# Ethernet.net
KiCad netlist of a schematic drawn in Altium Designer
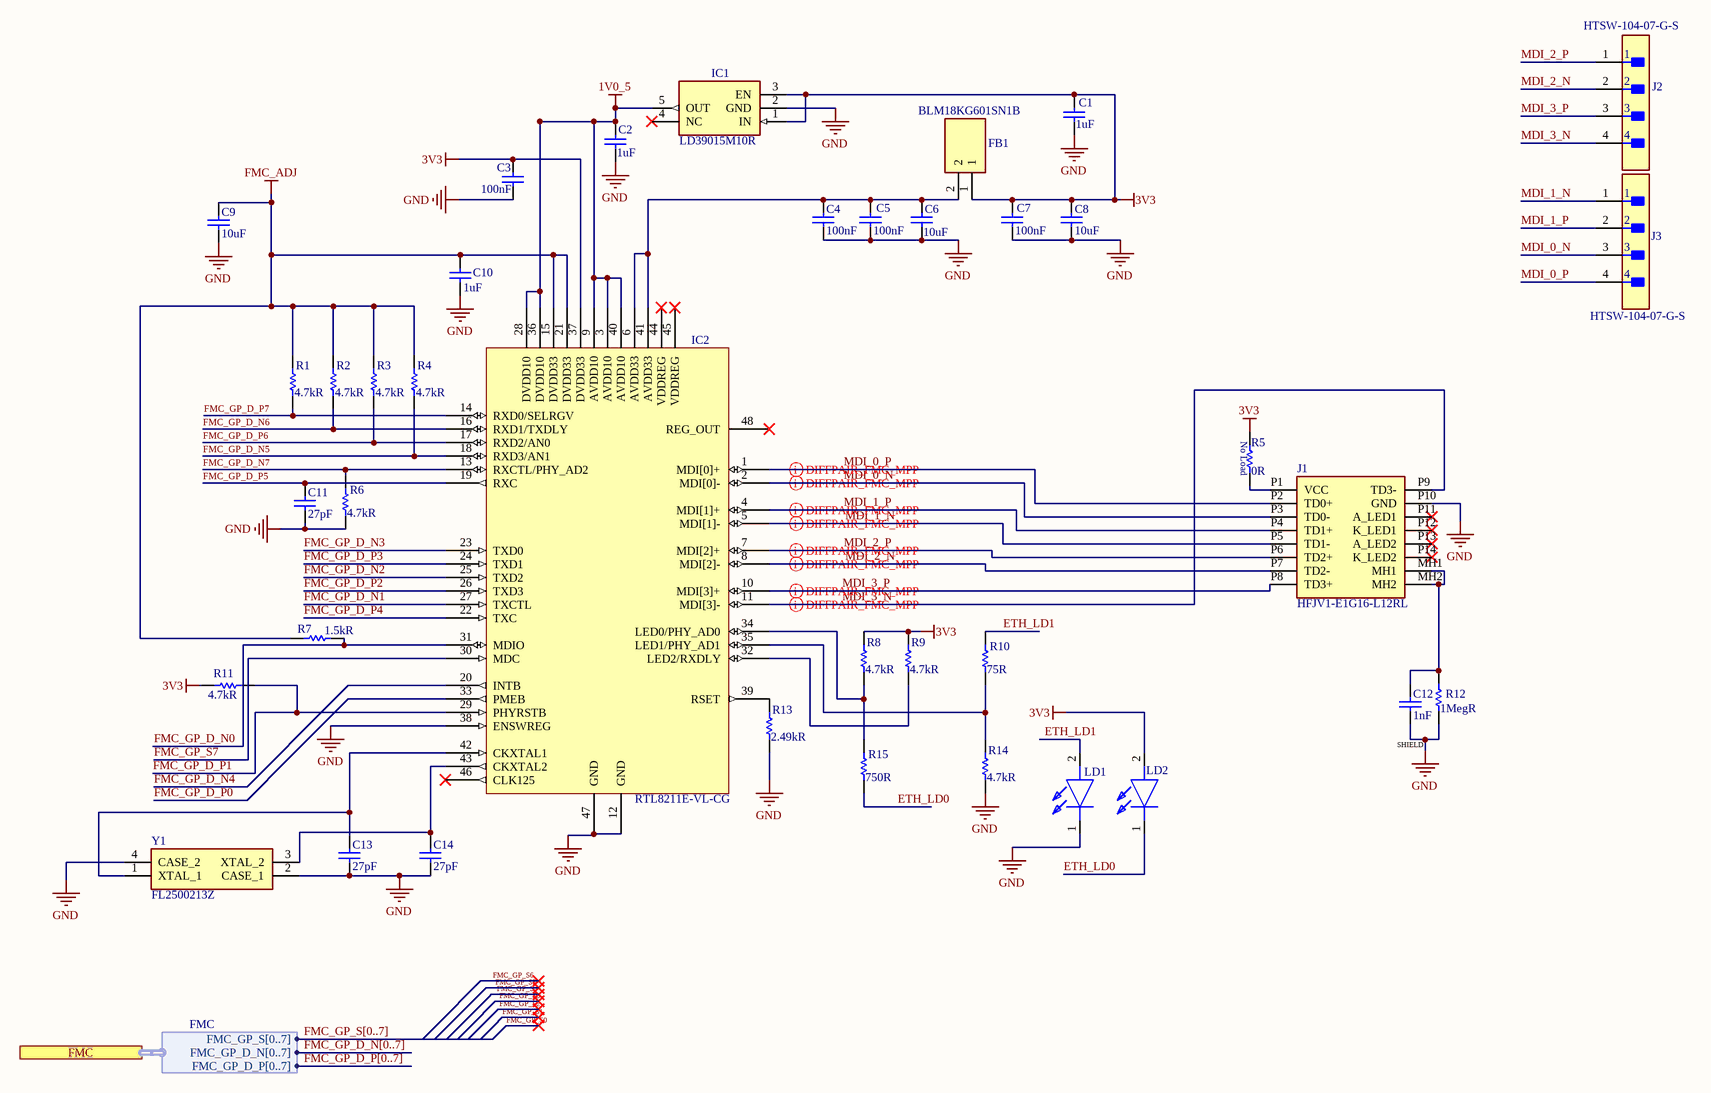
[diagram p0: Ethernet.SchDoc]

(export (version "E")
  (design (tool "Eeschema 10.0.6"))
  (components
    (comp (ref "C1")
      (value "1uF")
      (footprint "CAPC1005X60X30LL05T10")
      (fields
        (field (name "PART NUMBER") "C0402C105K9PACTU")
        (field (name "MANUFACTURER") "Kemet")
        (field (name "TOLERANCE") "10%")
      )
      (libsource (lib "Altium Content Vault") (part "CAP"))
    )
    (comp (ref "C2")
      (value "1uF")
      (footprint "CAPC1005X60X30LL05T10")
      (fields
        (field (name "PART NUMBER") "C0402C105K9PACTU")
        (field (name "MANUFACTURER") "Kemet")
        (field (name "TOLERANCE") "10%")
      )
      (libsource (lib "Altium Content Vault") (part "CAP"))
    )
    (comp (ref "C3")
      (value "100nF")
      (footprint "CAPC1050X55X23LL05T13")
      (description "Chip Capacitor, 100 nF, +/- 10%, 16 V, -55 to 125 degC, 0402 (1005 Metric), RoHS, Tape and Reel")
      (fields
        (field (name "MANUFACTURER") "Samsung Electro-Mechanics")
        (field (name "MANUFACTURER PART NUMBER") "CL05B104KO5NNNC")
      )
      (libsource (lib "Altium Content Vault") (part "CAP-NP-2"))
    )
    (comp (ref "C4")
      (value "100nF")
      (footprint "CAPC1050X55X23LL05T13")
      (description "Chip Capacitor, 100 nF, +/- 10%, 16 V, -55 to 125 degC, 0402 (1005 Metric), RoHS, Tape and Reel")
      (fields
        (field (name "MANUFACTURER") "Samsung Electro-Mechanics")
        (field (name "MANUFACTURER PART NUMBER") "CL05B104KO5NNNC")
      )
      (libsource (lib "Altium Content Vault") (part "CAP-NP-2"))
    )
    (comp (ref "C5")
      (value "100nF")
      (footprint "CAPC1050X55X23LL05T13")
      (description "Chip Capacitor, 100 nF, +/- 10%, 16 V, -55 to 125 degC, 0402 (1005 Metric), RoHS, Tape and Reel")
      (fields
        (field (name "MANUFACTURER") "Samsung Electro-Mechanics")
        (field (name "MANUFACTURER PART NUMBER") "CL05B104KO5NNNC")
      )
      (libsource (lib "Altium Content Vault") (part "CAP-NP-2"))
    )
    (comp (ref "C6")
      (value "10uF")
      (footprint "CAPC1608X90X35LL15T15")
      (fields
        (field (name "MANUFACTURER") "AVX Interconnect / Elco")
        (field (name "PART NUMBER") "06036D106MAT2A")
        (field (name "TOLERANCE") "20%")
      )
      (libsource (lib "Altium Content Vault") (part "CAP"))
    )
    (comp (ref "C7")
      (value "100nF")
      (footprint "CAPC1050X55X23LL05T13")
      (description "Chip Capacitor, 100 nF, +/- 10%, 16 V, -55 to 125 degC, 0402 (1005 Metric), RoHS, Tape and Reel")
      (fields
        (field (name "MANUFACTURER") "Samsung Electro-Mechanics")
        (field (name "MANUFACTURER PART NUMBER") "CL05B104KO5NNNC")
      )
      (libsource (lib "Altium Content Vault") (part "CAP-NP-2"))
    )
    (comp (ref "C8")
      (value "10uF")
      (footprint "CAPC1608X90X35LL15T15")
      (fields
        (field (name "MANUFACTURER") "AVX Interconnect / Elco")
        (field (name "PART NUMBER") "06036D106MAT2A")
        (field (name "TOLERANCE") "20%")
      )
      (libsource (lib "Altium Content Vault") (part "CAP"))
    )
    (comp (ref "C9")
      (value "10uF")
      (footprint "CAPC1608X90X35LL15T15")
      (fields
        (field (name "MANUFACTURER") "AVX Interconnect / Elco")
        (field (name "PART NUMBER") "06036D106MAT2A")
        (field (name "TOLERANCE") "20%")
      )
      (libsource (lib "Altium Content Vault") (part "CAP"))
    )
    (comp (ref "C10")
      (value "1uF")
      (footprint "CAPC1005X60X30LL05T10")
      (fields
        (field (name "PART NUMBER") "C0402C105K9PACTU")
        (field (name "MANUFACTURER") "Kemet")
        (field (name "TOLERANCE") "10%")
      )
      (libsource (lib "Altium Content Vault") (part "CAP"))
    )
    (comp (ref "C11")
      (value "27pF")
      (footprint "CAPC1005X56X25LL10T15")
      (description "0402YA270JAT2A")
      (fields (field (name "MANUFACTURER") "AVX Interconnect / Elco"))
      (libsource (lib "first") (part "CMP-2008-02772-1"))
    )
    (comp (ref "C12")
      (value "1nF")
      (footprint "CAPC0603(1608)100_L")
      (description "CAP 1nF 10V ±1% 0603 (1608 Metric) Thickness 1mm SMD")
      (fields (field (name "TOLERANCE") "Â±1%"))
      (libsource (lib "first") (part "CMP-1035-01871-1"))
    )
    (comp (ref "C13")
      (value "27pF")
      (footprint "CAPC1005X56X25LL10T15")
      (description "0402YA270JAT2A")
      (fields (field (name "MANUFACTURER") "AVX Interconnect / Elco"))
      (libsource (lib "first") (part "CMP-2008-02772-1"))
    )
    (comp (ref "C14")
      (value "27pF")
      (footprint "CAPC1005X56X25LL10T15")
      (description "0402YA270JAT2A")
      (fields (field (name "MANUFACTURER") "AVX Interconnect / Elco"))
      (libsource (lib "first") (part "CMP-2008-02772-1"))
    )
    (comp (ref "FB1")
      (value "BLM18KG601SN1B")
      (footprint "BLM18EG121SH1D")
      (description "Ferrite Bead")
      (libsource (lib "*") (part "BLM18KG601SN1B"))
    )
    (comp (ref "IC1")
      (value "LD39015M10R")
      (footprint "SOT95P280X145-5N")
      (description "Integrated Circuit")
      (fields (field (name "MOUSER PART NUMBER") "511-LD39015M10R"))
      (libsource (lib "first") (part "LD39015M10R"))
    )
    (comp (ref "IC2")
      (value "RTL8211E-VL-CG")
      (footprint "QFN40P600X600X100-49N")
      (description "GbE PHY with RGMII interface & EEE feature, 1.8V & 1.5V")
      (fields (field (name "MANUFACTURER") "Realtek"))
      (libsource (lib "first") (part "RTL8211E-VL-CG"))
    )
    (comp (ref "J1")
      (value "HFJV1-E1G16-L12RL")
      (footprint "HFJV1E1G16L12RL")
      (description "Connector")
      (fields (field (name "MOUSER PART NUMBER") "493-HFJV1-E1G16L12RL"))
      (libsource (lib "first") (part "HFJV1-E1G16-L12RL"))
    )
    (comp (ref "J2")
      (value "HTSW-104-07-G-S")
      (footprint "FP-HTSW-104-07-G-S-MFG")
      (description "CONN HEADER VERT 4POS 2.54MM")
      (libsource (lib "first") (part "CMP-02766-001776-1"))
    )
    (comp (ref "J3")
      (value "HTSW-104-07-G-S")
      (footprint "FP-HTSW-104-07-G-S-MFG")
      (description "CONN HEADER VERT 4POS 2.54MM")
      (libsource (lib "first") (part "CMP-02766-001776-1"))
    )
    (comp (ref "LD1")
      (value "AA3021LSYSK_J3-TR")
      (footprint "AA3021LSYSKJ3TR")
      (description "LED")
      (fields
        (field (name "MANUFACTURER_PART_NUMBER") "AA3021LSYSK/J3-TR")
        (field (name "MOUSER PART NUMBER") "604-AA3021LSYSK/J3TR")
      )
      (libsource (lib "first") (part "AA3021LSYSK_J3-TR"))
    )
    (comp (ref "LD2")
      (value "CSL1901VW1")
      (footprint "LEDC1608X65N")
      (description "LED")
      (fields (field (name "MOUSER PART NUMBER") "755-CSL1901VW1"))
      (libsource (lib "first") (part "CSL1901VW1"))
    )
    (comp (ref "R1")
      (value "4.7kR")
      (footprint "RESC0603X28X15LL05T05")
      (description "CRCW02014K70FKED")
      (fields (field (name "MANUFACTURER") "Vishay Dale"))
      (libsource (lib "first") (part "CMP-2004-00671-1"))
    )
    (comp (ref "R2")
      (value "4.7kR")
      (footprint "RESC0603X28X15LL05T05")
      (description "CRCW02014K70FKED")
      (fields (field (name "MANUFACTURER") "Vishay Dale"))
      (libsource (lib "first") (part "CMP-2004-00671-1"))
    )
    (comp (ref "R3")
      (value "4.7kR")
      (footprint "RESC0603X28X15LL05T05")
      (description "CRCW02014K70FKED")
      (fields (field (name "MANUFACTURER") "Vishay Dale"))
      (libsource (lib "first") (part "CMP-2004-00671-1"))
    )
    (comp (ref "R4")
      (value "4.7kR")
      (footprint "RESC0603X28X15LL05T05")
      (description "CRCW02014K70FKED")
      (fields (field (name "MANUFACTURER") "Vishay Dale"))
      (libsource (lib "first") (part "CMP-2004-00671-1"))
    )
    (comp (ref "R5")
      (value "0R")
      (footprint "RESC1005X40X25LL05T05")
      (description "ERJ2GE0R00X Chip Resistor, 0 Ohm, 0.1 W, -55 to 155 degC, 0402 (1005 Metric), RoHS, Tape and Reel")
      (fields (field (name "MANUFACTURER") "Panasonic") (field (name "TOLERANCE") "5%"))
      (libsource (lib "first") (part "CMP-2000-07451-1"))
    )
    (comp (ref "R6")
      (value "4.7kR")
      (footprint "RESC0603X28X15LL05T05")
      (description "CRCW02014K70FKED")
      (fields (field (name "MANUFACTURER") "Vishay Dale"))
      (libsource (lib "first") (part "CMP-2004-00671-1"))
    )
    (comp (ref "R7")
      (value "1.5kR")
      (footprint "RESC0603X28N")
      (description "CRCW02011K50FKED")
      (fields (field (name "MOUSER PART NUMBER") "71-CRCW02011K50FKED"))
      (libsource (lib "first") (part "CRCW02011K50FKED"))
    )
    (comp (ref "R8")
      (value "4.7kR")
      (footprint "RESC0603X28X15LL05T05")
      (description "CRCW02014K70FKED")
      (fields (field (name "MANUFACTURER") "Vishay Dale"))
      (libsource (lib "first") (part "CMP-2004-00671-1"))
    )
    (comp (ref "R9")
      (value "4.7kR")
      (footprint "RESC0603X28X15LL05T05")
      (description "CRCW02014K70FKED")
      (fields (field (name "MANUFACTURER") "Vishay Dale"))
      (libsource (lib "first") (part "CMP-2004-00671-1"))
    )
    (comp (ref "R10")
      (value "75R")
      (footprint "RESC0603X28X15LL05T05")
      (description "CRCW02014K70FKED")
      (fields (field (name "MANUFACTURER") "Vishay Dale"))
      (libsource (lib "first") (part "CMP-2004-00671-1"))
    )
    (comp (ref "R11")
      (value "4.7kR")
      (footprint "RESC0603X28X15LL05T05")
      (description "CRCW02014K70FKED")
      (fields (field (name "MANUFACTURER") "Vishay Dale"))
      (libsource (lib "first") (part "CMP-2004-00671-1"))
    )
    (comp (ref "R12")
      (value "1MegR")
      (footprint "RESC0603X28X15LL05T05")
      (description "CRCW02011M00FKED")
      (fields (field (name "MANUFACTURER") "Vishay Dale") (field (name "PART NUMBER") "CRCW02014K70FKED"))
      (libsource (lib "first") (part "CMP-2004-00671-1"))
    )
    (comp (ref "R13")
      (value "2.49kR")
      (footprint "RESC0603X28X15LL05T05")
      (description "CRCW02012K49FKED")
      (fields (field (name "MANUFACTURER") "Vishay Dale") (field (name "PART NUMBER") "CRCW02014K70FKED"))
      (libsource (lib "first") (part "CMP-2004-00671-1"))
    )
    (comp (ref "R14")
      (value "4.7kR")
      (footprint "RESC0603X28X15LL05T05")
      (description "CRCW02014K70FKED")
      (fields (field (name "MANUFACTURER") "Vishay Dale"))
      (libsource (lib "first") (part "CMP-2004-00671-1"))
    )
    (comp (ref "R15")
      (value "750R")
      (footprint "RESC0603X28X15LL05T05")
      (description "CRCW02014K70FKED")
      (fields (field (name "MANUFACTURER") "Vishay Dale"))
      (libsource (lib "first") (part "CMP-2004-00671-1"))
    )
    (comp (ref "Y1")
      (value "FL2500213Z")
      (footprint "FL2500213Z")
      (description "Crystal or Oscillator")
      (fields (field (name "MOUSER PART NUMBER") "729-FL2500213Z"))
      (libsource (lib "first") (part "FL2500213Z"))
    )
  )
  (nets
    (net (code "2") (name "/ETH_LD0") (class "Default")
      (node (ref "LD2") (pin "1") (pinfunction "K_1") (pintype "passive"))
      (node (ref "R15") (pin "1") (pinfunction "1_1") (pintype "passive"))
    )
    (net (code "3") (name "/ETH_LD1") (class "Default")
      (node (ref "LD1") (pin "2") (pinfunction "A_2") (pintype "passive"))
      (node (ref "R10") (pin "2") (pinfunction "2_2") (pintype "passive"))
    )
    (net (code "4") (name "/FMC_GP_D_N0") (class "Default")
      (node (ref "IC2") (pin "31") (pinfunction "MDIO_31") (pintype "bidirectional"))
      (node (ref "R7") (pin "2") (pinfunction "2_2") (pintype "passive"))
    )
    (net (code "5") (name "/FMC_GP_D_N1") (class "Default")
      (node (ref "IC2") (pin "27") (pinfunction "TXCTL_27") (pintype "input"))
    )
    (net (code "6") (name "/FMC_GP_D_N2") (class "Default")
      (node (ref "IC2") (pin "25") (pinfunction "TXD2_25") (pintype "input"))
    )
    (net (code "7") (name "/FMC_GP_D_N3") (class "Default")
      (node (ref "IC2") (pin "23") (pinfunction "TXD0_23") (pintype "input"))
    )
    (net (code "8") (name "/FMC_GP_D_N4") (class "Default")
      (node (ref "IC2") (pin "20") (pinfunction "INTB_20") (pintype "output"))
    )
    (net (code "9") (name "/FMC_GP_D_N5") (class "Default")
      (node (ref "IC2") (pin "18") (pinfunction "RXD3/AN1_18") (pintype "bidirectional"))
      (node (ref "R4") (pin "1") (pinfunction "1_1") (pintype "passive"))
    )
    (net (code "10") (name "/FMC_GP_D_N6") (class "Default")
      (node (ref "IC2") (pin "16") (pinfunction "RXD1/TXDLY_16") (pintype "bidirectional"))
      (node (ref "R2") (pin "1") (pinfunction "1_1") (pintype "passive"))
    )
    (net (code "11") (name "/FMC_GP_D_N7") (class "Default")
      (node (ref "IC2") (pin "13") (pinfunction "RXCTL/PHY_AD2_13") (pintype "bidirectional"))
      (node (ref "R6") (pin "2") (pinfunction "2_2") (pintype "passive"))
    )
    (net (code "12") (name "/FMC_GP_D_P0") (class "Default")
      (node (ref "IC2") (pin "33") (pinfunction "PMEB_33") (pintype "output"))
    )
    (net (code "13") (name "/FMC_GP_D_P1") (class "Default")
      (node (ref "IC2") (pin "29") (pinfunction "PHYRSTB_29") (pintype "input"))
      (node (ref "R11") (pin "1") (pinfunction "1_1") (pintype "passive"))
    )
    (net (code "14") (name "/FMC_GP_D_P2") (class "Default")
      (node (ref "IC2") (pin "26") (pinfunction "TXD3_26") (pintype "input"))
    )
    (net (code "15") (name "/FMC_GP_D_P3") (class "Default")
      (node (ref "IC2") (pin "24") (pinfunction "TXD1_24") (pintype "input"))
    )
    (net (code "16") (name "/FMC_GP_D_P4") (class "Default")
      (node (ref "IC2") (pin "22") (pinfunction "TXC_22") (pintype "input"))
    )
    (net (code "17") (name "/FMC_GP_D_P5") (class "Default")
      (node (ref "C11") (pin "2") (pinfunction "2_2") (pintype "passive"))
      (node (ref "IC2") (pin "19") (pinfunction "RXC_19") (pintype "output"))
    )
    (net (code "18") (name "/FMC_GP_D_P6") (class "Default")
      (node (ref "IC2") (pin "17") (pinfunction "RXD2/AN0_17") (pintype "bidirectional"))
      (node (ref "R3") (pin "1") (pinfunction "1_1") (pintype "passive"))
    )
    (net (code "19") (name "/FMC_GP_D_P7") (class "Default")
      (node (ref "IC2") (pin "14") (pinfunction "RXD0/SELRGV_14") (pintype "bidirectional"))
      (node (ref "R1") (pin "1") (pinfunction "1_1") (pintype "passive"))
    )
    (net (code "28") (name "/FMC_GP_S7") (class "Default")
      (node (ref "IC2") (pin "30") (pinfunction "MDC_30") (pintype "input"))
    )
    (net (code "31") (name "/MDI_0_N") (class "Default")
      (node (ref "IC2") (pin "2") (pinfunction "MDI[0]-_2") (pintype "bidirectional"))
      (node (ref "J1") (pin "P3") (pinfunction "TD0-_P3") (pintype "passive"))
      (node (ref "J3") (pin "3") (pinfunction "3_3") (pintype "passive"))
    )
    (net (code "32") (name "/MDI_0_P") (class "Default")
      (node (ref "IC2") (pin "1") (pinfunction "MDI[0]+_1") (pintype "bidirectional"))
      (node (ref "J1") (pin "P2") (pinfunction "TD0+_P2") (pintype "passive"))
      (node (ref "J3") (pin "4") (pinfunction "4_4") (pintype "passive"))
    )
    (net (code "33") (name "/MDI_1_N") (class "Default")
      (node (ref "IC2") (pin "5") (pinfunction "MDI[1]-_5") (pintype "bidirectional"))
      (node (ref "J1") (pin "P5") (pinfunction "TD1-_P5") (pintype "passive"))
      (node (ref "J3") (pin "1") (pinfunction "1_1") (pintype "passive"))
    )
    (net (code "34") (name "/MDI_1_P") (class "Default")
      (node (ref "IC2") (pin "4") (pinfunction "MDI[1]+_4") (pintype "bidirectional"))
      (node (ref "J1") (pin "P4") (pinfunction "TD1+_P4") (pintype "passive"))
      (node (ref "J3") (pin "2") (pinfunction "2_2") (pintype "passive"))
    )
    (net (code "35") (name "/MDI_2_N") (class "Default")
      (node (ref "IC2") (pin "8") (pinfunction "MDI[2]-_8") (pintype "bidirectional"))
      (node (ref "J1") (pin "P7") (pinfunction "TD2-_P7") (pintype "passive"))
      (node (ref "J2") (pin "2") (pinfunction "2_2") (pintype "passive"))
    )
    (net (code "36") (name "/MDI_2_P") (class "Default")
      (node (ref "IC2") (pin "7") (pinfunction "MDI[2]+_7") (pintype "bidirectional"))
      (node (ref "J1") (pin "P6") (pinfunction "TD2+_P6") (pintype "passive"))
      (node (ref "J2") (pin "1") (pinfunction "1_1") (pintype "passive"))
    )
    (net (code "37") (name "/MDI_3_N") (class "Default")
      (node (ref "IC2") (pin "11") (pinfunction "MDI[3]-_11") (pintype "bidirectional"))
      (node (ref "J1") (pin "P9") (pinfunction "TD3-_P9") (pintype "passive"))
      (node (ref "J2") (pin "4") (pinfunction "4_4") (pintype "passive"))
    )
    (net (code "38") (name "/MDI_3_P") (class "Default")
      (node (ref "IC2") (pin "10") (pinfunction "MDI[3]+_10") (pintype "bidirectional"))
      (node (ref "J1") (pin "P8") (pinfunction "TD3+_P8") (pintype "passive"))
      (node (ref "J2") (pin "3") (pinfunction "3_3") (pintype "passive"))
    )
    (net (code "40") (name "1V0_5") (class "Default")
      (node (ref "C2") (pin "2") (pinfunction "2_2") (pintype "passive"))
      (node (ref "IC1") (pin "5") (pinfunction "OUT_5") (pintype "output"))
      (node (ref "IC2") (pin "28") (pinfunction "DVDD10_28") (pintype "passive"))
      (node (ref "IC2") (pin "3") (pinfunction "AVDD10_3") (pintype "passive"))
      (node (ref "IC2") (pin "36") (pinfunction "DVDD10_36") (pintype "passive"))
      (node (ref "IC2") (pin "40") (pinfunction "AVDD10_40") (pintype "passive"))
      (node (ref "IC2") (pin "9") (pinfunction "AVDD10_9") (pintype "passive"))
    )
    (net (code "41") (name "3V3") (class "Default")
      (node (ref "C1") (pin "2") (pinfunction "2_2") (pintype "passive"))
      (node (ref "C3") (pin "2") (pinfunction "2_2") (pintype "passive"))
      (node (ref "C7") (pin "2") (pinfunction "2_2") (pintype "passive"))
      (node (ref "C8") (pin "2") (pinfunction "2_2") (pintype "passive"))
      (node (ref "FB1") (pin "1") (pinfunction "1_1") (pintype "passive"))
      (node (ref "IC1") (pin "1") (pinfunction "IN_1") (pintype "input"))
      (node (ref "IC1") (pin "3") (pinfunction "EN_3") (pintype "passive"))
      (node (ref "IC2") (pin "37") (pinfunction "DVDD33_37") (pintype "passive"))
      (node (ref "LD2") (pin "2") (pinfunction "A_2") (pintype "passive"))
      (node (ref "R11") (pin "2") (pinfunction "2_2") (pintype "passive"))
      (node (ref "R5") (pin "2") (pinfunction "2_2") (pintype "passive"))
      (node (ref "R8") (pin "2") (pinfunction "2_2") (pintype "passive"))
      (node (ref "R9") (pin "2") (pinfunction "2_2") (pintype "passive"))
    )
    (net (code "42") (name "FMC_ADJ") (class "Default")
      (node (ref "C10") (pin "2") (pinfunction "2_2") (pintype "passive"))
      (node (ref "C9") (pin "2") (pinfunction "2_2") (pintype "passive"))
      (node (ref "IC2") (pin "15") (pinfunction "DVDD33_15") (pintype "passive"))
      (node (ref "IC2") (pin "21") (pinfunction "DVDD33_21") (pintype "passive"))
      (node (ref "R1") (pin "2") (pinfunction "2_2") (pintype "passive"))
      (node (ref "R2") (pin "2") (pinfunction "2_2") (pintype "passive"))
      (node (ref "R3") (pin "2") (pinfunction "2_2") (pintype "passive"))
      (node (ref "R4") (pin "2") (pinfunction "2_2") (pintype "passive"))
      (node (ref "R7") (pin "1") (pinfunction "1_1") (pintype "passive"))
    )
    (net (code "43") (name "GND") (class "Default")
      (node (ref "C1") (pin "1") (pinfunction "1_1") (pintype "passive"))
      (node (ref "C10") (pin "1") (pinfunction "1_1") (pintype "passive"))
      (node (ref "C11") (pin "1") (pinfunction "1_1") (pintype "passive"))
      (node (ref "C12") (pin "1") (pinfunction "1_1") (pintype "passive"))
      (node (ref "C13") (pin "1") (pinfunction "1_1") (pintype "passive"))
      (node (ref "C14") (pin "1") (pinfunction "1_1") (pintype "passive"))
      (node (ref "C2") (pin "1") (pinfunction "1_1") (pintype "passive"))
      (node (ref "C3") (pin "1") (pinfunction "1_1") (pintype "passive"))
      (node (ref "C4") (pin "1") (pinfunction "1_1") (pintype "passive"))
      (node (ref "C5") (pin "1") (pinfunction "1_1") (pintype "passive"))
      (node (ref "C6") (pin "1") (pinfunction "1_1") (pintype "passive"))
      (node (ref "C7") (pin "1") (pinfunction "1_1") (pintype "passive"))
      (node (ref "C8") (pin "1") (pinfunction "1_1") (pintype "passive"))
      (node (ref "C9") (pin "1") (pinfunction "1_1") (pintype "passive"))
      (node (ref "IC1") (pin "2") (pinfunction "GND_2") (pintype "power_in"))
      (node (ref "IC2") (pin "12") (pinfunction "GND_12") (pintype "passive"))
      (node (ref "IC2") (pin "38") (pinfunction "ENSWREG_38") (pintype "input"))
      (node (ref "IC2") (pin "47") (pinfunction "GND_47") (pintype "passive"))
      (node (ref "J1") (pin "P10") (pinfunction "GND_P10") (pintype "passive"))
      (node (ref "LD1") (pin "1") (pinfunction "K_1") (pintype "passive"))
      (node (ref "R12") (pin "1") (pinfunction "1_1") (pintype "passive"))
      (node (ref "R13") (pin "1") (pinfunction "1_1") (pintype "passive"))
      (node (ref "R14") (pin "1") (pinfunction "1_1") (pintype "passive"))
      (node (ref "R6") (pin "1") (pinfunction "1_1") (pintype "passive"))
      (node (ref "Y1") (pin "2") (pinfunction "CASE_1_2") (pintype "passive"))
      (node (ref "Y1") (pin "4") (pinfunction "CASE_2_4") (pintype "passive"))
    )
    (net (code "44") (name "Net-(C4-Pad2)") (class "Default")
      (node (ref "C4") (pin "2") (pinfunction "2_2") (pintype "passive"))
      (node (ref "C5") (pin "2") (pinfunction "2_2") (pintype "passive"))
      (node (ref "C6") (pin "2") (pinfunction "2_2") (pintype "passive"))
      (node (ref "FB1") (pin "2") (pinfunction "2_2") (pintype "passive"))
      (node (ref "IC2") (pin "41") (pinfunction "AVDD33_41") (pintype "passive"))
      (node (ref "IC2") (pin "6") (pinfunction "AVDD33_6") (pintype "passive"))
    )
    (net (code "45") (name "Net-(C12-Pad2)") (class "Default")
      (node (ref "C12") (pin "2") (pinfunction "2_2") (pintype "passive"))
      (node (ref "J1") (pin "MH1") (pinfunction "MH1_MH1") (pintype "passive"))
      (node (ref "J1") (pin "MH2") (pinfunction "MH2_MH2") (pintype "passive"))
      (node (ref "R12") (pin "2") (pinfunction "2_2") (pintype "passive"))
    )
    (net (code "46") (name "Net-(IC2-CKXTAL1)") (class "Default")
      (node (ref "C13") (pin "2") (pinfunction "2_2") (pintype "passive"))
      (node (ref "IC2") (pin "42") (pinfunction "CKXTAL1_42") (pintype "input"))
      (node (ref "Y1") (pin "1") (pinfunction "XTAL_1_1") (pintype "passive"))
    )
    (net (code "47") (name "Net-(IC2-CKXTAL2)") (class "Default")
      (node (ref "C14") (pin "2") (pinfunction "2_2") (pintype "passive"))
      (node (ref "IC2") (pin "43") (pinfunction "CKXTAL2_43") (pintype "output"))
      (node (ref "Y1") (pin "3") (pinfunction "XTAL_2_3") (pintype "passive"))
    )
    (net (code "48") (name "Net-(IC2-LED0{slash}PHY_AD0)") (class "Default")
      (node (ref "IC2") (pin "34") (pinfunction "LED0/PHY_AD0_34") (pintype "bidirectional"))
      (node (ref "R15") (pin "2") (pinfunction "2_2") (pintype "passive"))
      (node (ref "R8") (pin "1") (pinfunction "1_1") (pintype "passive"))
    )
    (net (code "49") (name "Net-(IC2-LED1{slash}PHY_AD1)") (class "Default")
      (node (ref "IC2") (pin "35") (pinfunction "LED1/PHY_AD1_35") (pintype "bidirectional"))
      (node (ref "R10") (pin "1") (pinfunction "1_1") (pintype "passive"))
      (node (ref "R14") (pin "2") (pinfunction "2_2") (pintype "passive"))
    )
    (net (code "50") (name "Net-(IC2-LED2{slash}RXDLY)") (class "Default")
      (node (ref "IC2") (pin "32") (pinfunction "LED2/RXDLY_32") (pintype "bidirectional"))
      (node (ref "R9") (pin "1") (pinfunction "1_1") (pintype "passive"))
    )
    (net (code "51") (name "Net-(IC2-RSET)") (class "Default")
      (node (ref "IC2") (pin "39") (pinfunction "RSET_39") (pintype "output"))
      (node (ref "R13") (pin "2") (pinfunction "2_2") (pintype "passive"))
    )
    (net (code "52") (name "Net-(J1-VCC)") (class "Default")
      (node (ref "J1") (pin "P1") (pinfunction "VCC_P1") (pintype "passive"))
      (node (ref "R5") (pin "1") (pinfunction "1_1") (pintype "passive"))
    )
    (net (code "53") (name "unconnected-(IC1-NC-Pad4)") (class "Default")
      (node (ref "IC1") (pin "4") (pinfunction "NC_4") (pintype "passive+no_connect"))
    )
    (net (code "54") (name "unconnected-(IC2-CLK125-Pad46)") (class "Default")
      (node (ref "IC2") (pin "46") (pinfunction "CLK125_46") (pintype "output+no_connect"))
    )
    (net (code "55") (name "unconnected-(IC2-REG_OUT-Pad48)") (class "Default")
      (node (ref "IC2") (pin "48") (pinfunction "REG_OUT_48") (pintype "passive+no_connect"))
    )
    (net (code "56") (name "unconnected-(IC2-VDDREG-Pad44)") (class "Default")
      (node (ref "IC2") (pin "44") (pinfunction "VDDREG_44") (pintype "passive+no_connect"))
    )
    (net (code "57") (name "unconnected-(IC2-VDDREG-Pad45)") (class "Default")
      (node (ref "IC2") (pin "45") (pinfunction "VDDREG_45") (pintype "passive+no_connect"))
    )
    (net (code "58") (name "unconnected-(J1-A_LED1-PadP11)") (class "Default")
      (node (ref "J1") (pin "P11") (pinfunction "A_LED1_P11") (pintype "passive+no_connect"))
    )
    (net (code "59") (name "unconnected-(J1-A_LED2-PadP13)") (class "Default")
      (node (ref "J1") (pin "P13") (pinfunction "A_LED2_P13") (pintype "passive+no_connect"))
    )
    (net (code "60") (name "unconnected-(J1-K_LED1-PadP12)") (class "Default")
      (node (ref "J1") (pin "P12") (pinfunction "K_LED1_P12") (pintype "passive+no_connect"))
    )
    (net (code "61") (name "unconnected-(J1-K_LED2-PadP14)") (class "Default")
      (node (ref "J1") (pin "P14") (pinfunction "K_LED2_P14") (pintype "passive+no_connect"))
    )
  )
)
